# Xonik_Noise_A6_w_logo_v2_0.net
KiCad netlist of a schematic drawn in EAGLE
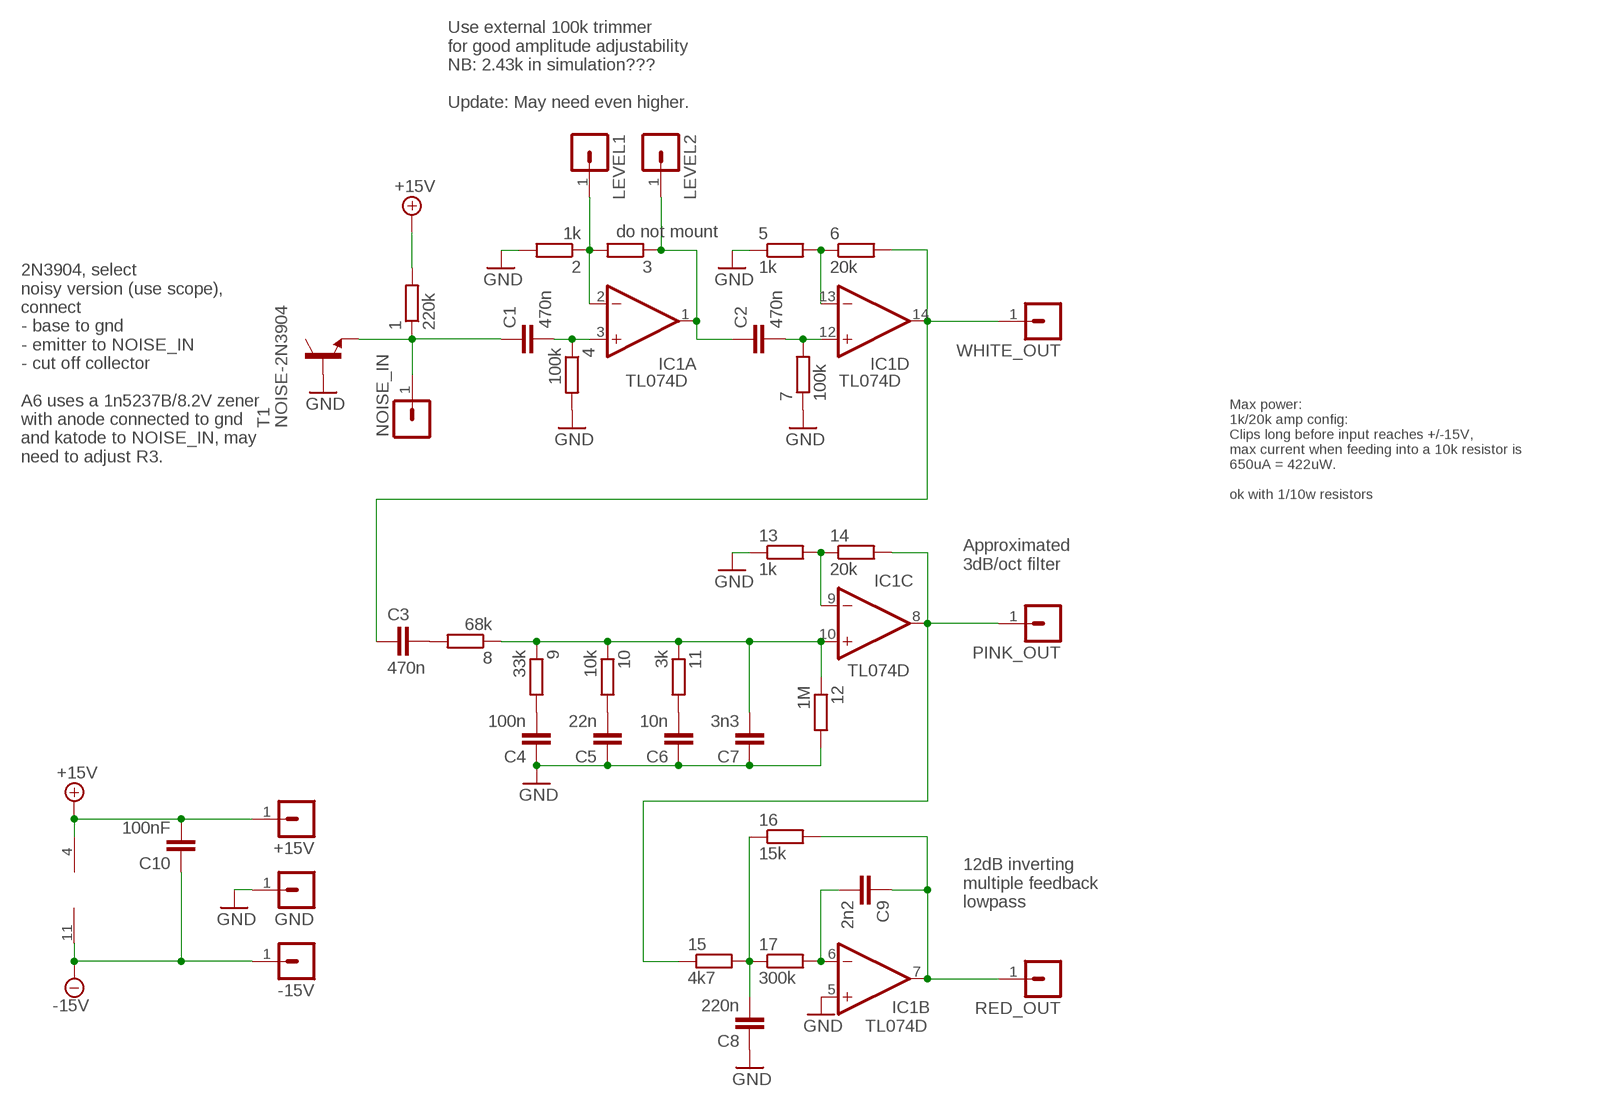
[diagram p0: schematic, sheet 1]

(export (version "E")
  (design (tool "Eeschema 10.0.6"))
  (components
    (comp (ref "+15V")
      (value "MA01-1JP")
      (footprint "eagle-import:SIP-PIN01-1J")
      (libsource (lib "eagle-import") (part "MA01-1JP"))
    )
    (comp (ref "-15V")
      (value "MA01-1JP")
      (footprint "eagle-import:SIP-PIN01-1J")
      (libsource (lib "eagle-import") (part "MA01-1JP"))
    )
    (comp (ref "1")
      (value "220k")
      (footprint "eagle-import:R0805")
      (libsource (lib "eagle-import") (part "R-EU_R0805"))
    )
    (comp (ref "2")
      (value "1k")
      (footprint "eagle-import:R0805")
      (libsource (lib "eagle-import") (part "R-EU_R0805"))
    )
    (comp (ref "3")
      (value "do not mount")
      (footprint "eagle-import:R0805")
      (libsource (lib "eagle-import") (part "R-EU_R0805"))
    )
    (comp (ref "4")
      (value "100k")
      (footprint "eagle-import:R0805")
      (libsource (lib "eagle-import") (part "R-EU_R0805"))
    )
    (comp (ref "5")
      (value "1k")
      (footprint "eagle-import:R0805")
      (libsource (lib "eagle-import") (part "R-EU_R0805"))
    )
    (comp (ref "6")
      (value "20k")
      (footprint "eagle-import:R0805")
      (libsource (lib "eagle-import") (part "R-EU_R0805"))
    )
    (comp (ref "7")
      (value "100k")
      (footprint "eagle-import:R0805")
      (libsource (lib "eagle-import") (part "R-EU_R0805"))
    )
    (comp (ref "8")
      (value "68k")
      (footprint "eagle-import:R0805")
      (libsource (lib "eagle-import") (part "R-EU_R0805"))
    )
    (comp (ref "9")
      (value "33k")
      (footprint "eagle-import:R0805")
      (libsource (lib "eagle-import") (part "R-EU_R0805"))
    )
    (comp (ref "10")
      (value "10k")
      (footprint "eagle-import:R0805")
      (libsource (lib "eagle-import") (part "R-EU_R0805"))
    )
    (comp (ref "11")
      (value "3k")
      (footprint "eagle-import:R0805")
      (libsource (lib "eagle-import") (part "R-EU_R0805"))
    )
    (comp (ref "12")
      (value "1M")
      (footprint "eagle-import:R0805")
      (libsource (lib "eagle-import") (part "R-EU_R0805"))
    )
    (comp (ref "13")
      (value "1k")
      (footprint "eagle-import:R0805")
      (libsource (lib "eagle-import") (part "R-EU_R0805"))
    )
    (comp (ref "14")
      (value "20k")
      (footprint "eagle-import:R0805")
      (libsource (lib "eagle-import") (part "R-EU_R0805"))
    )
    (comp (ref "15")
      (value "4k7")
      (footprint "eagle-import:R0805")
      (libsource (lib "eagle-import") (part "R-EU_R0805"))
    )
    (comp (ref "16")
      (value "15k")
      (footprint "eagle-import:R0805")
      (libsource (lib "eagle-import") (part "R-EU_R0805"))
    )
    (comp (ref "17")
      (value "300k")
      (footprint "eagle-import:R0805")
      (libsource (lib "eagle-import") (part "R-EU_R0805"))
    )
    (comp (ref "C1")
      (value "470n")
      (footprint "eagle-import:C0805")
      (libsource (lib "eagle-import") (part "C-EUC0805"))
    )
    (comp (ref "C2")
      (value "470n")
      (footprint "eagle-import:C0805")
      (libsource (lib "eagle-import") (part "C-EUC0805"))
    )
    (comp (ref "C3")
      (value "470n")
      (footprint "eagle-import:C0805")
      (libsource (lib "eagle-import") (part "C-EUC0805"))
    )
    (comp (ref "C4")
      (value "100n")
      (footprint "eagle-import:C0805")
      (libsource (lib "eagle-import") (part "C-EUC0805"))
    )
    (comp (ref "C5")
      (value "22n")
      (footprint "eagle-import:C0805")
      (libsource (lib "eagle-import") (part "C-EUC0805"))
    )
    (comp (ref "C6")
      (value "10n")
      (footprint "eagle-import:C0805")
      (libsource (lib "eagle-import") (part "C-EUC0805"))
    )
    (comp (ref "C7")
      (value "3n3")
      (footprint "eagle-import:C0805")
      (libsource (lib "eagle-import") (part "C-EUC0805"))
    )
    (comp (ref "C8")
      (value "220n")
      (footprint "eagle-import:C0805")
      (libsource (lib "eagle-import") (part "C-EUC0805"))
    )
    (comp (ref "C9")
      (value "2n2")
      (footprint "eagle-import:C0805")
      (libsource (lib "eagle-import") (part "C-EUC0805"))
    )
    (comp (ref "C10")
      (value "100nF")
      (footprint "eagle-import:C0603")
      (libsource (lib "eagle-import") (part "C-EUC0603"))
    )
    (comp (ref "GND")
      (value "MA01-1JP")
      (footprint "eagle-import:SIP-PIN01-1J")
      (libsource (lib "eagle-import") (part "MA01-1JP"))
    )
    (comp (ref "IC1")
      (value "TL074D")
      (footprint "eagle-import:SO14")
      (libsource (lib "eagle-import") (part "TL074D"))
    )
    (comp (ref "LEVEL1")
      (value "MA01-1JP")
      (footprint "eagle-import:SIP-PIN01-1J")
      (libsource (lib "eagle-import") (part "MA01-1JP"))
    )
    (comp (ref "LEVEL2")
      (value "MA01-1JP")
      (footprint "eagle-import:SIP-PIN01-1J")
      (libsource (lib "eagle-import") (part "MA01-1JP"))
    )
    (comp (ref "NOISE_IN")
      (value "MA01-1JP")
      (footprint "eagle-import:SIP-PIN01-1J")
      (libsource (lib "eagle-import") (part "MA01-1JP"))
    )
    (comp (ref "PINK_OUT")
      (value "MA01-1JP")
      (footprint "eagle-import:SIP-PIN01-1J")
      (libsource (lib "eagle-import") (part "MA01-1JP"))
    )
    (comp (ref "RED_OUT")
      (value "MA01-1JP")
      (footprint "eagle-import:SIP-PIN01-1J")
      (libsource (lib "eagle-import") (part "MA01-1JP"))
    )
    (comp (ref "T1")
      (value "NOISE-2N3904")
      (footprint "eagle-import:NOISE-2N3904-J")
      (libsource (lib "eagle-import") (part "NOISE-2N3904"))
    )
    (comp (ref "WHITE_OUT")
      (value "MA01-1JP")
      (footprint "eagle-import:SIP-PIN01-1J")
      (libsource (lib "eagle-import") (part "MA01-1JP"))
    )
  )
  (nets
    (net (code "1") (name "+15V") (class "Default")
      (node (ref "+15V") (pin "1") (pinfunction "1_1") (pintype "passive"))
      (node (ref "1") (pin "2") (pinfunction "2_2") (pintype "passive"))
      (node (ref "C10") (pin "2") (pinfunction "2_2") (pintype "passive"))
      (node (ref "IC1") (pin "4") (pinfunction "V+_4") (pintype "power_in"))
    )
    (net (code "2") (name "-15V") (class "Default")
      (node (ref "-15V") (pin "1") (pinfunction "1_1") (pintype "passive"))
      (node (ref "C10") (pin "1") (pinfunction "1_1") (pintype "passive"))
      (node (ref "IC1") (pin "11") (pinfunction "V-_11") (pintype "power_in"))
    )
    (net (code "3") (name "GND") (class "Default")
      (node (ref "12") (pin "2") (pinfunction "2_2") (pintype "passive"))
      (node (ref "13") (pin "1") (pinfunction "1_1") (pintype "passive"))
      (node (ref "2") (pin "2") (pinfunction "2_2") (pintype "passive"))
      (node (ref "4") (pin "2") (pinfunction "2_2") (pintype "passive"))
      (node (ref "5") (pin "1") (pinfunction "1_1") (pintype "passive"))
      (node (ref "7") (pin "1") (pinfunction "1_1") (pintype "passive"))
      (node (ref "C4") (pin "1") (pinfunction "1_1") (pintype "passive"))
      (node (ref "C5") (pin "1") (pinfunction "1_1") (pintype "passive"))
      (node (ref "C6") (pin "1") (pinfunction "1_1") (pintype "passive"))
      (node (ref "C7") (pin "1") (pinfunction "1_1") (pintype "passive"))
      (node (ref "C8") (pin "1") (pinfunction "1_1") (pintype "passive"))
      (node (ref "GND") (pin "1") (pinfunction "1_1") (pintype "passive"))
      (node (ref "IC1") (pin "5") (pinfunction "+IN_5") (pintype "input"))
      (node (ref "T1") (pin "B") (pinfunction "B_B") (pintype "passive"))
    )
    (net (code "4") (name "Net-(1-Pad1)") (class "Default")
      (node (ref "1") (pin "1") (pinfunction "1_1") (pintype "passive"))
      (node (ref "C1") (pin "1") (pinfunction "1_1") (pintype "passive"))
      (node (ref "NOISE_IN") (pin "1") (pinfunction "1_1") (pintype "passive"))
      (node (ref "T1") (pin "E") (pinfunction "E_E") (pintype "passive"))
    )
    (net (code "5") (name "Net-(8-Pad2)") (class "Default")
      (node (ref "8") (pin "2") (pinfunction "2_2") (pintype "passive"))
      (node (ref "C3") (pin "2") (pinfunction "2_2") (pintype "passive"))
    )
    (net (code "6") (name "Net-(9-Pad2)") (class "Default")
      (node (ref "9") (pin "2") (pinfunction "2_2") (pintype "passive"))
      (node (ref "C4") (pin "2") (pinfunction "2_2") (pintype "passive"))
    )
    (net (code "7") (name "Net-(10-Pad2)") (class "Default")
      (node (ref "10") (pin "2") (pinfunction "2_2") (pintype "passive"))
      (node (ref "C5") (pin "2") (pinfunction "2_2") (pintype "passive"))
    )
    (net (code "8") (name "Net-(11-Pad2)") (class "Default")
      (node (ref "11") (pin "2") (pinfunction "2_2") (pintype "passive"))
      (node (ref "C6") (pin "2") (pinfunction "2_2") (pintype "passive"))
    )
    (net (code "9") (name "Net-(15-Pad2)") (class "Default")
      (node (ref "15") (pin "2") (pinfunction "2_2") (pintype "passive"))
      (node (ref "16") (pin "1") (pinfunction "1_1") (pintype "passive"))
      (node (ref "17") (pin "1") (pinfunction "1_1") (pintype "passive"))
      (node (ref "C8") (pin "2") (pinfunction "2_2") (pintype "passive"))
    )
    (net (code "10") (name "Net-(IC1A-+IN)") (class "Default")
      (node (ref "4") (pin "1") (pinfunction "1_1") (pintype "passive"))
      (node (ref "C1") (pin "2") (pinfunction "2_2") (pintype "passive"))
      (node (ref "IC1") (pin "3") (pinfunction "+IN_3") (pintype "input"))
    )
    (net (code "11") (name "Net-(IC1A--IN)") (class "Default")
      (node (ref "2") (pin "1") (pinfunction "1_1") (pintype "passive"))
      (node (ref "3") (pin "2") (pinfunction "2_2") (pintype "passive"))
      (node (ref "IC1") (pin "2") (pinfunction "-IN_2") (pintype "input"))
      (node (ref "LEVEL1") (pin "1") (pinfunction "1_1") (pintype "passive"))
    )
    (net (code "12") (name "Net-(IC1A-OUT)") (class "Default")
      (node (ref "3") (pin "1") (pinfunction "1_1") (pintype "passive"))
      (node (ref "C2") (pin "1") (pinfunction "1_1") (pintype "passive"))
      (node (ref "IC1") (pin "1") (pinfunction "OUT_1") (pintype "output"))
      (node (ref "LEVEL2") (pin "1") (pinfunction "1_1") (pintype "passive"))
    )
    (net (code "13") (name "Net-(IC1B--IN)") (class "Default")
      (node (ref "17") (pin "2") (pinfunction "2_2") (pintype "passive"))
      (node (ref "C9") (pin "2") (pinfunction "2_2") (pintype "passive"))
      (node (ref "IC1") (pin "6") (pinfunction "-IN_6") (pintype "input"))
    )
    (net (code "14") (name "Net-(IC1B-OUT)") (class "Default")
      (node (ref "16") (pin "2") (pinfunction "2_2") (pintype "passive"))
      (node (ref "C9") (pin "1") (pinfunction "1_1") (pintype "passive"))
      (node (ref "IC1") (pin "7") (pinfunction "OUT_7") (pintype "output"))
      (node (ref "RED_OUT") (pin "1") (pinfunction "1_1") (pintype "passive"))
    )
    (net (code "15") (name "Net-(IC1C-+IN)") (class "Default")
      (node (ref "10") (pin "1") (pinfunction "1_1") (pintype "passive"))
      (node (ref "11") (pin "1") (pinfunction "1_1") (pintype "passive"))
      (node (ref "12") (pin "1") (pinfunction "1_1") (pintype "passive"))
      (node (ref "8") (pin "1") (pinfunction "1_1") (pintype "passive"))
      (node (ref "9") (pin "1") (pinfunction "1_1") (pintype "passive"))
      (node (ref "C7") (pin "2") (pinfunction "2_2") (pintype "passive"))
      (node (ref "IC1") (pin "10") (pinfunction "+IN_10") (pintype "input"))
    )
    (net (code "16") (name "Net-(IC1C--IN)") (class "Default")
      (node (ref "13") (pin "2") (pinfunction "2_2") (pintype "passive"))
      (node (ref "14") (pin "1") (pinfunction "1_1") (pintype "passive"))
      (node (ref "IC1") (pin "9") (pinfunction "-IN_9") (pintype "input"))
    )
    (net (code "17") (name "Net-(IC1C-OUT)") (class "Default")
      (node (ref "14") (pin "2") (pinfunction "2_2") (pintype "passive"))
      (node (ref "15") (pin "1") (pinfunction "1_1") (pintype "passive"))
      (node (ref "IC1") (pin "8") (pinfunction "OUT_8") (pintype "output"))
      (node (ref "PINK_OUT") (pin "1") (pinfunction "1_1") (pintype "passive"))
    )
    (net (code "18") (name "Net-(IC1D-+IN)") (class "Default")
      (node (ref "7") (pin "2") (pinfunction "2_2") (pintype "passive"))
      (node (ref "C2") (pin "2") (pinfunction "2_2") (pintype "passive"))
      (node (ref "IC1") (pin "12") (pinfunction "+IN_12") (pintype "input"))
    )
    (net (code "19") (name "Net-(IC1D--IN)") (class "Default")
      (node (ref "5") (pin "2") (pinfunction "2_2") (pintype "passive"))
      (node (ref "6") (pin "1") (pinfunction "1_1") (pintype "passive"))
      (node (ref "IC1") (pin "13") (pinfunction "-IN_13") (pintype "input"))
    )
    (net (code "20") (name "Net-(IC1D-OUT)") (class "Default")
      (node (ref "6") (pin "2") (pinfunction "2_2") (pintype "passive"))
      (node (ref "C3") (pin "1") (pinfunction "1_1") (pintype "passive"))
      (node (ref "IC1") (pin "14") (pinfunction "OUT_14") (pintype "output"))
      (node (ref "WHITE_OUT") (pin "1") (pinfunction "1_1") (pintype "passive"))
    )
  )
)
